# SingleMotorBoard.net
KiCad netlist of a schematic drawn in EAGLE
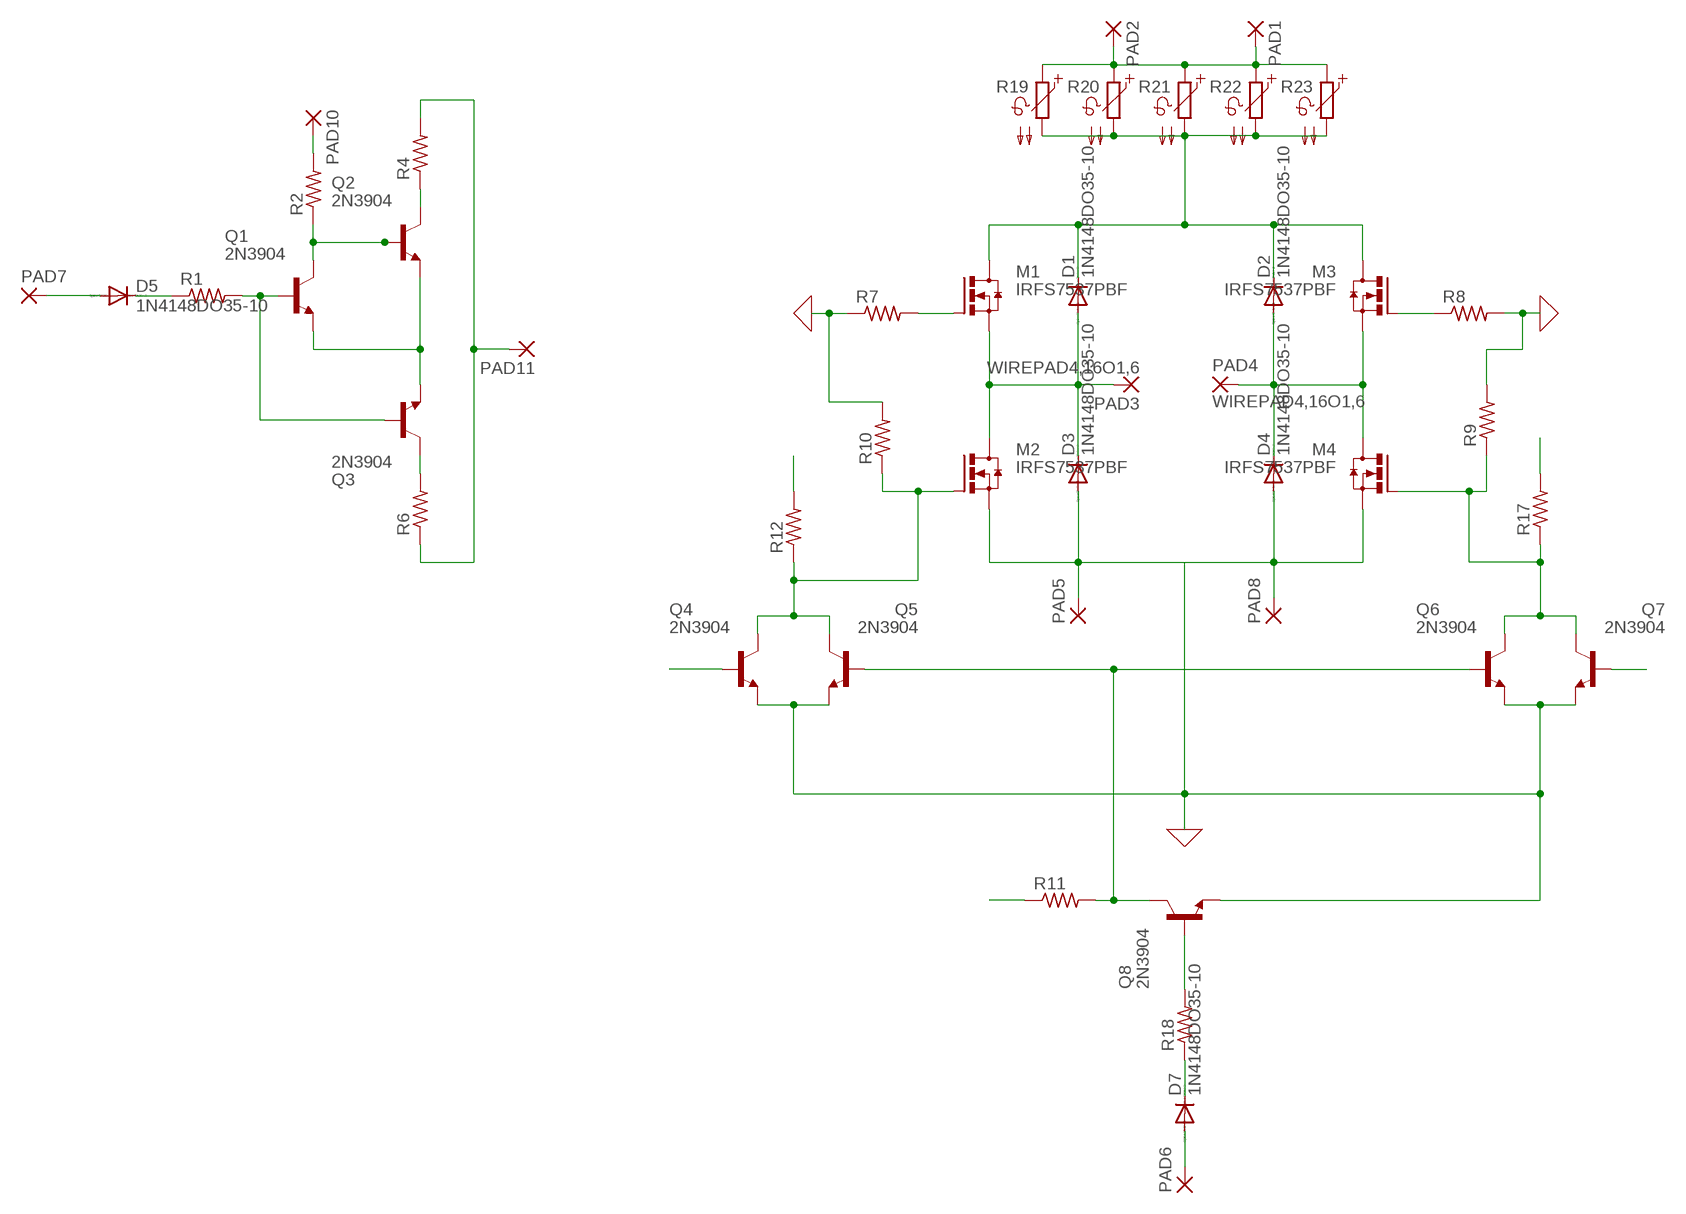
[diagram p0: schematic, sheet 1]

(export (version "E")
  (design (tool "Eeschema 10.0.6"))
  (components
    (comp (ref "D1")
      (value "1N4148DO35-10")
      (footprint "eagle-import:DO35-10")
      (libsource (lib "eagle-import") (part "1N4148DO35-10"))
    )
    (comp (ref "D2")
      (value "1N4148DO35-10")
      (footprint "eagle-import:DO35-10")
      (libsource (lib "eagle-import") (part "1N4148DO35-10"))
    )
    (comp (ref "D3")
      (value "1N4148DO35-10")
      (footprint "eagle-import:DO35-10")
      (libsource (lib "eagle-import") (part "1N4148DO35-10"))
    )
    (comp (ref "D4")
      (value "1N4148DO35-10")
      (footprint "eagle-import:DO35-10")
      (libsource (lib "eagle-import") (part "1N4148DO35-10"))
    )
    (comp (ref "D5")
      (value "1N4148DO35-10")
      (footprint "eagle-import:DO35-10")
      (libsource (lib "eagle-import") (part "1N4148DO35-10"))
    )
    (comp (ref "D7")
      (value "1N4148DO35-10")
      (footprint "eagle-import:DO35-10")
      (libsource (lib "eagle-import") (part "1N4148DO35-10"))
    )
    (comp (ref "M1")
      (value "IRFS7537PBF")
      (footprint "eagle-import:D2PACK")
      (libsource (lib "eagle-import") (part "IRFS7537PBF"))
    )
    (comp (ref "M2")
      (value "IRFS7537PBF")
      (footprint "eagle-import:D2PACK")
      (libsource (lib "eagle-import") (part "IRFS7537PBF"))
    )
    (comp (ref "M3")
      (value "IRFS7537PBF")
      (footprint "eagle-import:D2PACK")
      (libsource (lib "eagle-import") (part "IRFS7537PBF"))
    )
    (comp (ref "M4")
      (value "IRFS7537PBF")
      (footprint "eagle-import:D2PACK")
      (libsource (lib "eagle-import") (part "IRFS7537PBF"))
    )
    (comp (ref "PAD1")
      (value "3,81/1,4")
      (footprint "eagle-import:3,81_1,4")
      (libsource (lib "eagle-import") (part "3,81/1,4"))
    )
    (comp (ref "PAD2")
      (value "3,81/1,4")
      (footprint "eagle-import:3,81_1,4")
      (libsource (lib "eagle-import") (part "3,81/1,4"))
    )
    (comp (ref "PAD3")
      (value "WIREPAD4,16O1,6")
      (footprint "eagle-import:4,16O1,6")
      (libsource (lib "eagle-import") (part "WIREPAD4,16O1,6"))
    )
    (comp (ref "PAD4")
      (value "WIREPAD4,16O1,6")
      (footprint "eagle-import:4,16O1,6")
      (libsource (lib "eagle-import") (part "WIREPAD4,16O1,6"))
    )
    (comp (ref "PAD5")
      (value "3,81/1,4")
      (footprint "eagle-import:3,81_1,4")
      (libsource (lib "eagle-import") (part "3,81/1,4"))
    )
    (comp (ref "PAD6")
      (value "2,54/1,1")
      (footprint "eagle-import:2,54_1,1")
      (libsource (lib "eagle-import") (part "2,54/1,1"))
    )
    (comp (ref "PAD7")
      (value "2,54/1,0")
      (footprint "eagle-import:2,54_1,0")
      (libsource (lib "eagle-import") (part "2,54/1,0"))
    )
    (comp (ref "PAD8")
      (value "3,81/1,4")
      (footprint "eagle-import:3,81_1,4")
      (libsource (lib "eagle-import") (part "3,81/1,4"))
    )
    (comp (ref "PAD10")
      (value "2,54/1,1")
      (footprint "eagle-import:2,54_1,1")
      (libsource (lib "eagle-import") (part "2,54/1,1"))
    )
    (comp (ref "PAD11")
      (value "2,54/1,1")
      (footprint "eagle-import:2,54_1,1")
      (libsource (lib "eagle-import") (part "2,54/1,1"))
    )
    (comp (ref "Q1")
      (value "2N3904")
      (footprint "eagle-import:TO92")
      (libsource (lib "eagle-import") (part "2N3904"))
    )
    (comp (ref "Q2")
      (value "2N3904")
      (footprint "eagle-import:TO92")
      (libsource (lib "eagle-import") (part "2N3904"))
    )
    (comp (ref "Q3")
      (value "2N3904")
      (footprint "eagle-import:TO92")
      (libsource (lib "eagle-import") (part "2N3904"))
    )
    (comp (ref "Q4")
      (value "2N3904")
      (footprint "eagle-import:TO92")
      (libsource (lib "eagle-import") (part "2N3904"))
    )
    (comp (ref "Q5")
      (value "2N3904")
      (footprint "eagle-import:TO92")
      (libsource (lib "eagle-import") (part "2N3904"))
    )
    (comp (ref "Q6")
      (value "2N3904")
      (footprint "eagle-import:TO92")
      (libsource (lib "eagle-import") (part "2N3904"))
    )
    (comp (ref "Q7")
      (value "2N3904")
      (footprint "eagle-import:TO92")
      (libsource (lib "eagle-import") (part "2N3904"))
    )
    (comp (ref "Q8")
      (value "2N3904")
      (footprint "eagle-import:TO92")
      (libsource (lib "eagle-import") (part "2N3904"))
    )
    (comp (ref "R1")
      (value "R-US_0207/7")
      (footprint "eagle-import:0207_7")
      (libsource (lib "eagle-import") (part "R-US_0207/7"))
    )
    (comp (ref "R2")
      (value "R-US_0207/7")
      (footprint "eagle-import:0207_7")
      (libsource (lib "eagle-import") (part "R-US_0207/7"))
    )
    (comp (ref "R4")
      (value "R-US_0207/7")
      (footprint "eagle-import:0207_7")
      (libsource (lib "eagle-import") (part "R-US_0207/7"))
    )
    (comp (ref "R6")
      (value "R-US_0207/7")
      (footprint "eagle-import:0207_7")
      (libsource (lib "eagle-import") (part "R-US_0207/7"))
    )
    (comp (ref "R7")
      (value "R-US_0207/7")
      (footprint "eagle-import:0207_7")
      (libsource (lib "eagle-import") (part "R-US_0207/7"))
    )
    (comp (ref "R8")
      (value "R-US_0207/7")
      (footprint "eagle-import:0207_7")
      (libsource (lib "eagle-import") (part "R-US_0207/7"))
    )
    (comp (ref "R9")
      (value "R-US_0207/7")
      (footprint "eagle-import:0207_7")
      (libsource (lib "eagle-import") (part "R-US_0207/7"))
    )
    (comp (ref "R10")
      (value "R-US_0207/7")
      (footprint "eagle-import:0207_7")
      (libsource (lib "eagle-import") (part "R-US_0207/7"))
    )
    (comp (ref "R11")
      (value "R-US_0207/7")
      (footprint "eagle-import:0207_7")
      (libsource (lib "eagle-import") (part "R-US_0207/7"))
    )
    (comp (ref "R12")
      (value "R-US_0207/7")
      (footprint "eagle-import:0207_7")
      (libsource (lib "eagle-import") (part "R-US_0207/7"))
    )
    (comp (ref "R17")
      (value "R-US_0207/7")
      (footprint "eagle-import:0207_7")
      (libsource (lib "eagle-import") (part "resistor_348_R-US_0207/7"))
    )
    (comp (ref "R18")
      (value "R-US_0207/7")
      (footprint "eagle-import:0207_7")
      (libsource (lib "eagle-import") (part "R-US_0207/7"))
    )
    (comp (ref "R19")
      (value "PTC660A")
      (footprint "eagle-import:P660A")
      (libsource (lib "eagle-import") (part "PTC660A"))
    )
    (comp (ref "R20")
      (value "PTC660A")
      (footprint "eagle-import:P660A")
      (libsource (lib "eagle-import") (part "PTC660A"))
    )
    (comp (ref "R21")
      (value "PTC660A")
      (footprint "eagle-import:P660A")
      (libsource (lib "eagle-import") (part "PTC660A"))
    )
    (comp (ref "R22")
      (value "PTC660A")
      (footprint "eagle-import:P660A")
      (libsource (lib "eagle-import") (part "PTC660A"))
    )
    (comp (ref "R23")
      (value "PTC660A")
      (footprint "eagle-import:P660A")
      (libsource (lib "eagle-import") (part "PTC660A"))
    )
  )
  (nets
    (net (code "1") (name "/BB") (class "Default")
      (node (ref "Q1") (pin "2") (pinfunction "B_2") (pintype "passive"))
      (node (ref "Q3") (pin "2") (pinfunction "B_2") (pintype "passive"))
      (node (ref "Q4") (pin "2") (pinfunction "B_2") (pintype "passive"))
      (node (ref "R1") (pin "2") (pinfunction "2_2") (pintype "passive"))
    )
    (net (code "2") (name "/BF") (class "Default")
      (node (ref "M3") (pin "1") (pinfunction "G_1") (pintype "passive"))
      (node (ref "Q3") (pin "1") (pinfunction "C_1") (pintype "passive"))
      (node (ref "R6") (pin "2") (pinfunction "2_2") (pintype "passive"))
      (node (ref "R8") (pin "1") (pinfunction "1_1") (pintype "passive"))
    )
    (net (code "3") (name "/FB") (class "Default")
      (node (ref "Q1") (pin "1") (pinfunction "C_1") (pintype "passive"))
      (node (ref "Q2") (pin "2") (pinfunction "B_2") (pintype "passive"))
      (node (ref "Q7") (pin "2") (pinfunction "B_2") (pintype "passive"))
      (node (ref "R2") (pin "1") (pinfunction "1_1") (pintype "passive"))
    )
    (net (code "4") (name "/FF") (class "Default")
      (node (ref "M1") (pin "1") (pinfunction "G_1") (pintype "passive"))
      (node (ref "Q2") (pin "1") (pinfunction "C_1") (pintype "passive"))
      (node (ref "R4") (pin "1") (pinfunction "1_1") (pintype "passive"))
      (node (ref "R7") (pin "2") (pinfunction "2_2") (pintype "passive"))
    )
    (net (code "5") (name "/VG") (class "Default")
      (node (ref "PAD11") (pin "1") (pinfunction "P_1") (pintype "passive"))
      (node (ref "R12") (pin "2") (pinfunction "2_2") (pintype "passive"))
      (node (ref "R17") (pin "2") (pinfunction "2_2") (pintype "passive"))
      (node (ref "R4") (pin "2") (pinfunction "2_2") (pintype "passive"))
      (node (ref "R6") (pin "1") (pinfunction "1_1") (pintype "passive"))
    )
    (net (code "6") (name "/VSW") (class "Default")
      (node (ref "PAD10") (pin "1") (pinfunction "P_1") (pintype "passive"))
      (node (ref "R11") (pin "1") (pinfunction "1_1") (pintype "passive"))
      (node (ref "R2") (pin "2") (pinfunction "2_2") (pintype "passive"))
    )
    (net (code "7") (name "GND") (class "Default")
      (node (ref "D3") (pin "A") (pinfunction "A_A") (pintype "passive"))
      (node (ref "D4") (pin "A") (pinfunction "A_A") (pintype "passive"))
      (node (ref "M2") (pin "3") (pinfunction "S_3") (pintype "passive"))
      (node (ref "M4") (pin "3") (pinfunction "S_3") (pintype "passive"))
      (node (ref "PAD5") (pin "1") (pinfunction "P_1") (pintype "passive"))
      (node (ref "PAD8") (pin "1") (pinfunction "P_1") (pintype "passive"))
      (node (ref "Q1") (pin "3") (pinfunction "E_3") (pintype "passive"))
      (node (ref "Q2") (pin "3") (pinfunction "E_3") (pintype "passive"))
      (node (ref "Q3") (pin "3") (pinfunction "E_3") (pintype "passive"))
      (node (ref "Q4") (pin "3") (pinfunction "E_3") (pintype "passive"))
      (node (ref "Q5") (pin "3") (pinfunction "E_3") (pintype "passive"))
      (node (ref "Q6") (pin "3") (pinfunction "E_3") (pintype "passive"))
      (node (ref "Q7") (pin "3") (pinfunction "E_3") (pintype "passive"))
      (node (ref "Q8") (pin "3") (pinfunction "E_3") (pintype "passive"))
      (node (ref "R10") (pin "2") (pinfunction "2_2") (pintype "passive"))
      (node (ref "R7") (pin "1") (pinfunction "1_1") (pintype "passive"))
      (node (ref "R8") (pin "2") (pinfunction "2_2") (pintype "passive"))
      (node (ref "R9") (pin "2") (pinfunction "2_2") (pintype "passive"))
    )
    (net (code "8") (name "Net-(D5-PadC)") (class "Default")
      (node (ref "D5") (pin "C") (pinfunction "C_C") (pintype "passive"))
      (node (ref "R1") (pin "1") (pinfunction "1_1") (pintype "passive"))
    )
    (net (code "9") (name "Net-(D7-PadC)") (class "Default")
      (node (ref "D7") (pin "C") (pinfunction "C_C") (pintype "passive"))
      (node (ref "R18") (pin "1") (pinfunction "1_1") (pintype "passive"))
    )
    (net (code "10") (name "Net-(M1-D)") (class "Default")
      (node (ref "D1") (pin "C") (pinfunction "C_C") (pintype "passive"))
      (node (ref "D2") (pin "C") (pinfunction "C_C") (pintype "passive"))
      (node (ref "M1") (pin "2") (pinfunction "D_2") (pintype "passive"))
      (node (ref "M3") (pin "2") (pinfunction "D_2") (pintype "passive"))
      (node (ref "R19") (pin "2") (pinfunction "2_2") (pintype "passive"))
      (node (ref "R20") (pin "2") (pinfunction "2_2") (pintype "passive"))
      (node (ref "R21") (pin "2") (pinfunction "2_2") (pintype "passive"))
      (node (ref "R22") (pin "2") (pinfunction "2_2") (pintype "passive"))
      (node (ref "R23") (pin "2") (pinfunction "2_2") (pintype "passive"))
    )
    (net (code "11") (name "Net-(M1-S)") (class "Default")
      (node (ref "D1") (pin "A") (pinfunction "A_A") (pintype "passive"))
      (node (ref "D3") (pin "C") (pinfunction "C_C") (pintype "passive"))
      (node (ref "M1") (pin "3") (pinfunction "S_3") (pintype "passive"))
      (node (ref "M2") (pin "2") (pinfunction "D_2") (pintype "passive"))
      (node (ref "PAD3") (pin "1") (pinfunction "P_1") (pintype "passive"))
    )
    (net (code "12") (name "Net-(M2-G)") (class "Default")
      (node (ref "M2") (pin "1") (pinfunction "G_1") (pintype "passive"))
      (node (ref "Q4") (pin "1") (pinfunction "C_1") (pintype "passive"))
      (node (ref "Q5") (pin "1") (pinfunction "C_1") (pintype "passive"))
      (node (ref "R10") (pin "1") (pinfunction "1_1") (pintype "passive"))
      (node (ref "R12") (pin "1") (pinfunction "1_1") (pintype "passive"))
    )
    (net (code "13") (name "Net-(M3-S)") (class "Default")
      (node (ref "D2") (pin "A") (pinfunction "A_A") (pintype "passive"))
      (node (ref "D4") (pin "C") (pinfunction "C_C") (pintype "passive"))
      (node (ref "M3") (pin "3") (pinfunction "S_3") (pintype "passive"))
      (node (ref "M4") (pin "2") (pinfunction "D_2") (pintype "passive"))
      (node (ref "PAD4") (pin "1") (pinfunction "P_1") (pintype "passive"))
    )
    (net (code "14") (name "Net-(M4-G)") (class "Default")
      (node (ref "M4") (pin "1") (pinfunction "G_1") (pintype "passive"))
      (node (ref "Q6") (pin "1") (pinfunction "C_1") (pintype "passive"))
      (node (ref "Q7") (pin "1") (pinfunction "C_1") (pintype "passive"))
      (node (ref "R17") (pin "1") (pinfunction "1_1") (pintype "passive"))
      (node (ref "R9") (pin "1") (pinfunction "1_1") (pintype "passive"))
    )
    (net (code "15") (name "Net-(PAD1-P)") (class "Default")
      (node (ref "PAD1") (pin "1") (pinfunction "P_1") (pintype "passive"))
      (node (ref "PAD2") (pin "1") (pinfunction "P_1") (pintype "passive"))
      (node (ref "R19") (pin "1") (pinfunction "1_1") (pintype "passive"))
      (node (ref "R20") (pin "1") (pinfunction "1_1") (pintype "passive"))
      (node (ref "R21") (pin "1") (pinfunction "1_1") (pintype "passive"))
      (node (ref "R22") (pin "1") (pinfunction "1_1") (pintype "passive"))
      (node (ref "R23") (pin "1") (pinfunction "1_1") (pintype "passive"))
    )
    (net (code "16") (name "Net-(PAD6-P)") (class "Default")
      (node (ref "D7") (pin "A") (pinfunction "A_A") (pintype "passive"))
      (node (ref "PAD6") (pin "1") (pinfunction "P_1") (pintype "passive"))
    )
    (net (code "17") (name "Net-(PAD7-P)") (class "Default")
      (node (ref "D5") (pin "A") (pinfunction "A_A") (pintype "passive"))
      (node (ref "PAD7") (pin "1") (pinfunction "P_1") (pintype "passive"))
    )
    (net (code "18") (name "Net-(Q5-B)") (class "Default")
      (node (ref "Q5") (pin "2") (pinfunction "B_2") (pintype "passive"))
      (node (ref "Q6") (pin "2") (pinfunction "B_2") (pintype "passive"))
      (node (ref "Q8") (pin "1") (pinfunction "C_1") (pintype "passive"))
      (node (ref "R11") (pin "2") (pinfunction "2_2") (pintype "passive"))
    )
    (net (code "19") (name "Net-(Q8-B)") (class "Default")
      (node (ref "Q8") (pin "2") (pinfunction "B_2") (pintype "passive"))
      (node (ref "R18") (pin "2") (pinfunction "2_2") (pintype "passive"))
    )
  )
)
